# Bitcoin_Wallet.net
KiCad netlist of a schematic drawn in Altium Designer
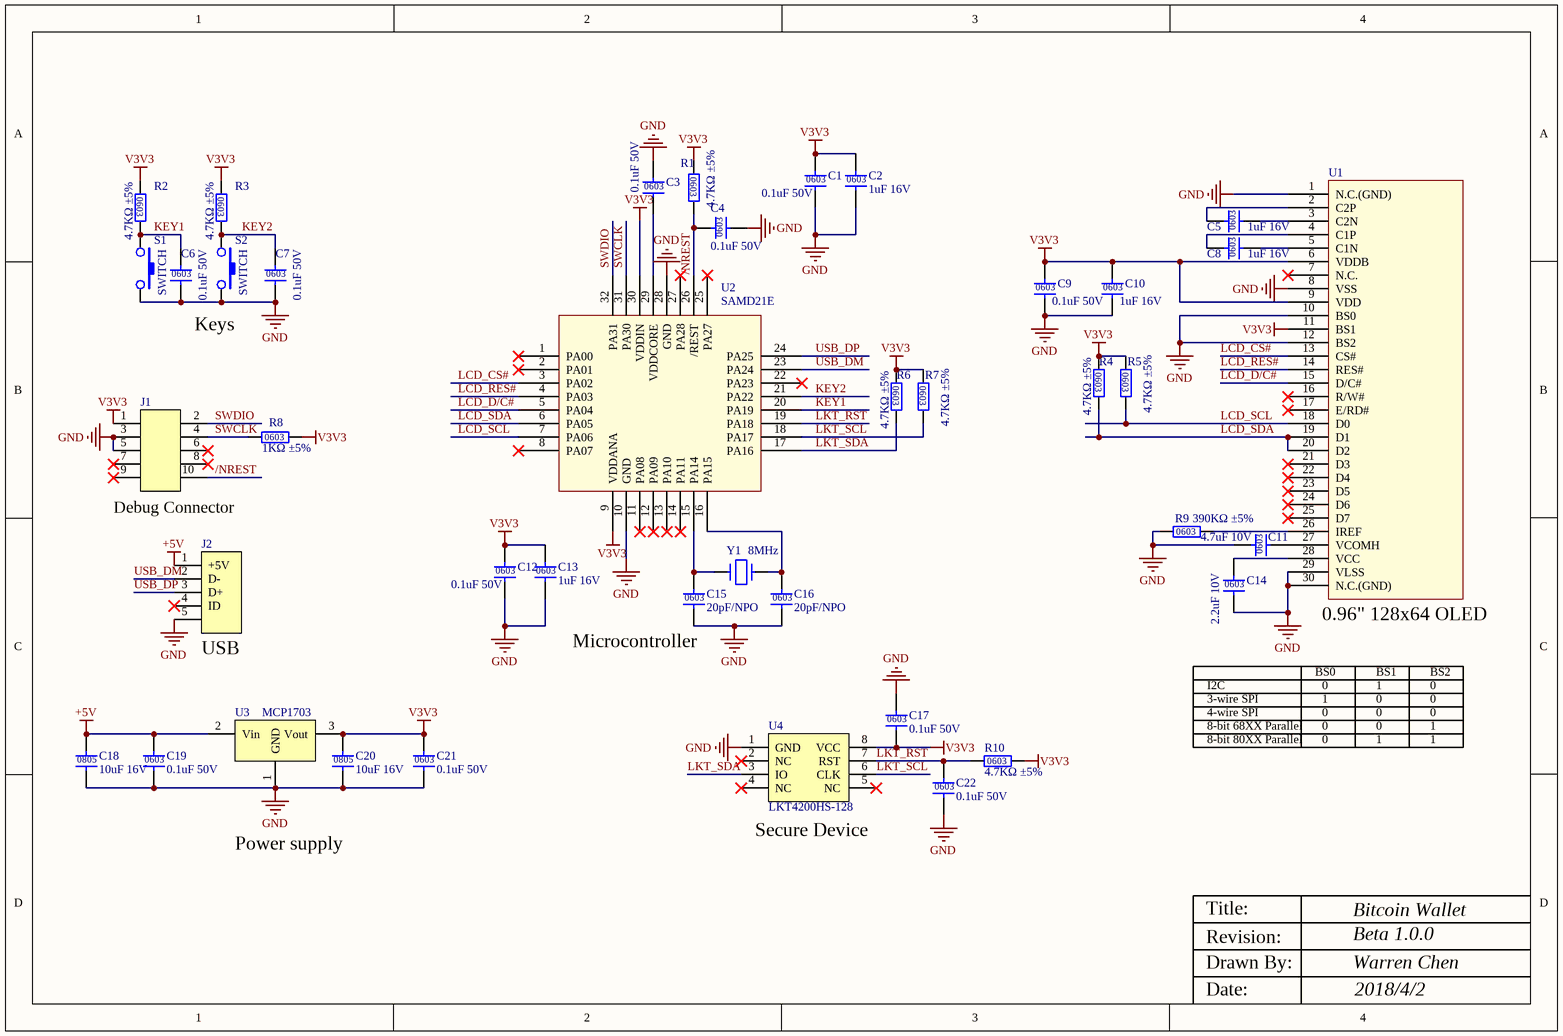
[diagram p0: Bitcoin Wallet.SchDoc]

(export (version "E")
  (design (tool "Eeschema 10.0.6"))
  (components
    (comp (ref "C1")
      (value "0.1uF 50V")
      (footprint "C-0603")
      (description "贴片电容 0.1uF 50V ±10% -55~+125℃ 0603 X7R CL10B104KB8NNNC")
      (libsource (lib "CLOU-BZ-BetaV0") (part "C-0.1uF 50V 0603"))
    )
    (comp (ref "C2")
      (value "1uF 16V")
      (footprint "C-0603")
      (description "贴片电容 1uF 16V ±10% -55~+125℃ 0603 X7R")
      (libsource (lib "CLOU-BZ-BetaV0") (part "C-1uF 16V 0603"))
    )
    (comp (ref "C3")
      (value "0.1uF 50V")
      (footprint "C-0603")
      (description "贴片电容 0.1uF 50V ±10% -55~+125℃ 0603 X7R CL10B104KB8NNNC")
      (libsource (lib "CLOU-BZ-BetaV0") (part "C-0.1uF 50V 0603"))
    )
    (comp (ref "C4")
      (value "0.1uF 50V")
      (footprint "C-0603")
      (description "贴片电容 0.1uF 50V ±10% -55~+125℃ 0603 X7R CL10B104KB8NNNC")
      (libsource (lib "CLOU-BZ-BetaV0") (part "C-0.1uF 50V 0603"))
    )
    (comp (ref "C5")
      (value "1uF 16V")
      (footprint "C-0603")
      (description "贴片电容 1uF 16V ±10% -55~+125℃ 0603 X7R")
      (libsource (lib "CLOU-BZ-BetaV0") (part "C-1uF 16V 0603"))
    )
    (comp (ref "C6")
      (value "0.1uF 50V")
      (footprint "C-0603")
      (description "贴片电容 0.1uF 50V ±10% -55~+125℃ 0603 X7R CL10B104KB8NNNC")
      (libsource (lib "CLOU-BZ-BetaV0") (part "C-0.1uF 50V 0603"))
    )
    (comp (ref "C7")
      (value "0.1uF 50V")
      (footprint "C-0603")
      (description "贴片电容 0.1uF 50V ±10% -55~+125℃ 0603 X7R CL10B104KB8NNNC")
      (libsource (lib "CLOU-BZ-BetaV0") (part "C-0.1uF 50V 0603"))
    )
    (comp (ref "C8")
      (value "1uF 16V")
      (footprint "C-0603")
      (description "贴片电容 1uF 16V ±10% -55~+125℃ 0603 X7R")
      (libsource (lib "CLOU-BZ-BetaV0") (part "C-1uF 16V 0603"))
    )
    (comp (ref "C9")
      (value "0.1uF 50V")
      (footprint "C-0603")
      (description "贴片电容 0.1uF 50V ±10% -55~+125℃ 0603 X7R CL10B104KB8NNNC")
      (libsource (lib "CLOU-BZ-BetaV0") (part "C-0.1uF 50V 0603"))
    )
    (comp (ref "C10")
      (value "1uF 16V")
      (footprint "C-0603")
      (description "贴片电容 1uF 16V ±10% -55~+125℃ 0603 X7R")
      (libsource (lib "CLOU-BZ-BetaV0") (part "C-1uF 16V 0603"))
    )
    (comp (ref "C11")
      (value "4.7uF 10V")
      (footprint "C-0603")
      (description "贴片电容 4.7uF 10V ±10% 0603 X5R")
      (libsource (lib "CLOU-BZ-BetaV0") (part "C-4.7uF 10V 0603"))
    )
    (comp (ref "C12")
      (value "0.1uF 50V")
      (footprint "C-0603")
      (description "贴片电容 0.1uF 50V ±10% -55~+125℃ 0603 X7R CL10B104KB8NNNC")
      (libsource (lib "CLOU-BZ-BetaV0") (part "C-0.1uF 50V 0603"))
    )
    (comp (ref "C13")
      (value "1uF 16V")
      (footprint "C-0603")
      (description "贴片电容 1uF 16V ±10% -55~+125℃ 0603 X7R")
      (libsource (lib "CLOU-BZ-BetaV0") (part "C-1uF 16V 0603"))
    )
    (comp (ref "C14")
      (value "2.2uF 10V")
      (footprint "C-0603")
      (description "贴片电容 2.2uF 10V ±10% 0603 X5R")
      (libsource (lib "CLOU-BZ-BetaV0") (part "C-2.2uF 10V 0603"))
    )
    (comp (ref "C15")
      (value "20pF/NPO")
      (footprint "C-0603")
      (description "贴片电容 20pF 50V ±5% -55~+125℃ 0603 NPO")
      (libsource (lib "CLOU-BZ-BetaV0") (part "C-20pF 50V 0603"))
    )
    (comp (ref "C16")
      (value "20pF/NPO")
      (footprint "C-0603")
      (description "贴片电容 20pF 50V ±5% -55~+125℃ 0603 NPO")
      (libsource (lib "CLOU-BZ-BetaV0") (part "C-20pF 50V 0603"))
    )
    (comp (ref "C17")
      (value "0.1uF 50V")
      (footprint "C-0603")
      (description "贴片电容 0.1uF 50V ±10% -55~+125℃ 0603 X7R CL10B104KB8NNNC")
      (libsource (lib "CLOU-BZ-BetaV0") (part "C-0.1uF 50V 0603"))
    )
    (comp (ref "C18")
      (value "10uF 16V")
      (footprint "C-0805")
      (description "贴片电容 10uF 16V ±10% -55~+125℃ 0805 X5R")
      (libsource (lib "CLOU-BZ-BetaV0") (part "C-10uF 16V 0805"))
    )
    (comp (ref "C19")
      (value "0.1uF 50V")
      (footprint "C-0603")
      (description "贴片电容 0.1uF 50V ±10% -55~+125℃ 0603 X7R CL10B104KB8NNNC")
      (libsource (lib "CLOU-BZ-BetaV0") (part "C-0.1uF 50V 0603"))
    )
    (comp (ref "C20")
      (value "10uF 16V")
      (footprint "C-0805")
      (description "贴片电容 10uF 16V ±10% -55~+125℃ 0805 X5R")
      (libsource (lib "CLOU-BZ-BetaV0") (part "C-10uF 16V 0805"))
    )
    (comp (ref "C21")
      (value "0.1uF 50V")
      (footprint "C-0603")
      (description "贴片电容 0.1uF 50V ±10% -55~+125℃ 0603 X7R CL10B104KB8NNNC")
      (libsource (lib "CLOU-BZ-BetaV0") (part "C-0.1uF 50V 0603"))
    )
    (comp (ref "C22")
      (value "0.1uF 50V")
      (footprint "C-0603")
      (description "贴片电容 0.1uF 50V ±10% -55~+125℃ 0603 X7R CL10B104KB8NNNC")
      (libsource (lib "CLOU-BZ-BetaV0") (part "C-0.1uF 50V 0603"))
    )
    (comp (ref "J1") (value "Debug Connector") (libsource (lib "SCHLIB") (part "CON2*5")))
    (comp (ref "J2") (value "USB") (libsource (lib "SCHLIB") (part "USB")))
    (comp (ref "R1")
      (value "4.7KΩ ±5%")
      (footprint "R-0603")
      (description "贴片电阻 4.7KΩ 1/10W ±5% ±200ppm 0603")
      (libsource (lib "CLOU-BZ-BetaV0") (part "R-4K7 0603 5%"))
    )
    (comp (ref "R2")
      (value "4.7KΩ ±5%")
      (footprint "R-0603")
      (description "贴片电阻 4.7KΩ 1/10W ±5% ±200ppm 0603")
      (libsource (lib "CLOU-BZ-BetaV0") (part "R-4K7 0603 5%"))
    )
    (comp (ref "R3")
      (value "4.7KΩ ±5%")
      (footprint "R-0603")
      (description "贴片电阻 4.7KΩ 1/10W ±5% ±200ppm 0603")
      (libsource (lib "CLOU-BZ-BetaV0") (part "R-4K7 0603 5%"))
    )
    (comp (ref "R4")
      (value "4.7KΩ ±5%")
      (footprint "R-0603")
      (description "贴片电阻 4.7KΩ 1/10W ±5% ±200ppm 0603")
      (libsource (lib "CLOU-BZ-BetaV0") (part "R-4K7 0603 5%"))
    )
    (comp (ref "R5")
      (value "4.7KΩ ±5%")
      (footprint "R-0603")
      (description "贴片电阻 4.7KΩ 1/10W ±5% ±200ppm 0603")
      (libsource (lib "CLOU-BZ-BetaV0") (part "R-4K7 0603 5%"))
    )
    (comp (ref "R6")
      (value "4.7KΩ ±5%")
      (footprint "R-0603")
      (description "贴片电阻 4.7KΩ 1/10W ±5% ±200ppm 0603")
      (libsource (lib "CLOU-BZ-BetaV0") (part "R-4K7 0603 5%"))
    )
    (comp (ref "R7")
      (value "4.7KΩ ±5%")
      (footprint "R-0603")
      (description "贴片电阻 4.7KΩ 1/10W ±5% ±200ppm 0603")
      (libsource (lib "CLOU-BZ-BetaV0") (part "R-4K7 0603 5%"))
    )
    (comp (ref "R8")
      (value "1KΩ ±5%")
      (footprint "R-0603")
      (description "贴片电阻 1KΩ 1/10W ±5% ±200ppm 0603")
      (libsource (lib "CLOU-BZ-BetaV0") (part "R-1K 0603 5%"))
    )
    (comp (ref "R9")
      (value "390KΩ ±5%")
      (footprint "R-0603")
      (description "贴片电阻 390KΩ 1/10W ±5% ±200ppm 0603")
      (libsource (lib "CLOU-BZ-BetaV0") (part "R-390K 0603 5%"))
    )
    (comp (ref "R10")
      (value "4.7KΩ ±5%")
      (footprint "R-0603")
      (description "贴片电阻 4.7KΩ 1/10W ±5% ±200ppm 0603")
      (libsource (lib "") (part "R-4K7 0603 5%_1"))
    )
    (comp (ref "S1")
      (value "SWITCH")
      (footprint "SW4-6X6-1")
      (description "开关（轻触）")
      (libsource (lib "NEW library") (part "SW_PB6.2*6.2_5"))
    )
    (comp (ref "S2")
      (value "SWITCH")
      (footprint "SW4-6X6-1")
      (description "开关（轻触）")
      (libsource (lib "NEW library") (part "SW_PB6.2*6.2_5"))
    )
    (comp (ref "U1") (value "0.96\" 128x64 OLED") (libsource (lib "SCHLIB") (part "Component_1")))
    (comp (ref "U2") (value "SAMD21E") (libsource (lib "SCHLIB") (part "SAMD21E")))
    (comp (ref "U3")
      (value "MCP1703")
      (footprint "IC-SOT-89")
      (description "HT7533-1 工业级 SOT-89 3.3V 100mA")
      (libsource (lib "CLOU-BZ-BetaV0") (part "U-HT7533-1"))
    )
    (comp (ref "U4") (value "LKT4200HS-128") (libsource (lib "SCHLIB") (part "LKT4200HS-128")))
    (comp (ref "Y1")
      (value "8MHz")
      (footprint "CRYSTAL2")
      (description "晶振")
      (libsource (lib "NEW library") (part "CRYSTAL_18.432M"))
    )
  )
  (nets
    (net (code "1") (name "+5V") (class "Default")
      (node (ref "C18") (pin "1") (pinfunction "1_1") (pintype "passive"))
      (node (ref "C19") (pin "1") (pinfunction "1_1") (pintype "passive"))
      (node (ref "J2") (pin "1") (pinfunction "+5V_1") (pintype "passive"))
      (node (ref "U3") (pin "2") (pinfunction "Vin_2") (pintype "passive"))
    )
    (net (code "2") (name "/KEY1") (class "Default")
      (node (ref "C6") (pin "1") (pinfunction "1_1") (pintype "passive"))
      (node (ref "R2") (pin "2") (pinfunction "2_2") (pintype "passive"))
      (node (ref "S1") (pin "2") (pinfunction "2_2") (pintype "passive"))
      (node (ref "U2") (pin "20") (pinfunction "PA19_20") (pintype "passive"))
    )
    (net (code "3") (name "/KEY2") (class "Default")
      (node (ref "C7") (pin "1") (pinfunction "1_1") (pintype "passive"))
      (node (ref "R3") (pin "2") (pinfunction "2_2") (pintype "passive"))
      (node (ref "S2") (pin "2") (pinfunction "2_2") (pintype "passive"))
      (node (ref "U2") (pin "21") (pinfunction "PA22_21") (pintype "passive"))
    )
    (net (code "4") (name "/LCD_CS#") (class "Default")
      (node (ref "U1") (pin "13") (pinfunction "CS#_13") (pintype "passive"))
      (node (ref "U2") (pin "3") (pinfunction "PA02_3") (pintype "passive"))
    )
    (net (code "5") (name "/LCD_D{slash}C#") (class "Default")
      (node (ref "U1") (pin "15") (pinfunction "D/C#_15") (pintype "passive"))
      (node (ref "U2") (pin "5") (pinfunction "PA04_5") (pintype "passive"))
    )
    (net (code "6") (name "/LCD_RES#") (class "Default")
      (node (ref "U1") (pin "14") (pinfunction "RES#_14") (pintype "passive"))
      (node (ref "U2") (pin "4") (pinfunction "PA03_4") (pintype "passive"))
    )
    (net (code "7") (name "/LCD_SCL") (class "Default")
      (node (ref "R5") (pin "2") (pinfunction "2_2") (pintype "passive"))
      (node (ref "U1") (pin "18") (pinfunction "D0_18") (pintype "passive"))
      (node (ref "U2") (pin "7") (pinfunction "PA06_7") (pintype "passive"))
    )
    (net (code "8") (name "/LCD_SDA") (class "Default")
      (node (ref "R4") (pin "2") (pinfunction "2_2") (pintype "passive"))
      (node (ref "U1") (pin "19") (pinfunction "D1_19") (pintype "passive"))
      (node (ref "U1") (pin "20") (pinfunction "D2_20") (pintype "passive"))
      (node (ref "U2") (pin "6") (pinfunction "PA05_6") (pintype "passive"))
    )
    (net (code "9") (name "/LKT_RST") (class "Default")
      (node (ref "C22") (pin "1") (pinfunction "1_1") (pintype "passive"))
      (node (ref "R10") (pin "1") (pinfunction "1_1") (pintype "passive"))
      (node (ref "U2") (pin "19") (pinfunction "PA18_19") (pintype "passive"))
      (node (ref "U4") (pin "7") (pinfunction "RST_7") (pintype "passive"))
    )
    (net (code "10") (name "/LKT_SCL") (class "Default")
      (node (ref "R7") (pin "2") (pinfunction "2_2") (pintype "passive"))
      (node (ref "U2") (pin "18") (pinfunction "PA17_18") (pintype "passive"))
      (node (ref "U4") (pin "6") (pinfunction "CLK_6") (pintype "passive"))
    )
    (net (code "11") (name "/LKT_SDA") (class "Default")
      (node (ref "R6") (pin "2") (pinfunction "2_2") (pintype "passive"))
      (node (ref "U2") (pin "17") (pinfunction "PA16_17") (pintype "passive"))
      (node (ref "U4") (pin "3") (pinfunction "IO_3") (pintype "passive"))
    )
    (net (code "12") (name "/SWCLK") (class "Default")
      (node (ref "J1") (pin "4") (pinfunction "4_4") (pintype "passive"))
      (node (ref "R8") (pin "1") (pinfunction "1_1") (pintype "passive"))
      (node (ref "U2") (pin "31") (pinfunction "PA30_31") (pintype "passive"))
    )
    (net (code "13") (name "/SWDIO") (class "Default")
      (node (ref "J1") (pin "2") (pinfunction "2_2") (pintype "passive"))
      (node (ref "U2") (pin "32") (pinfunction "PA31_32") (pintype "passive"))
    )
    (net (code "14") (name "/USB_DM") (class "Default")
      (node (ref "J2") (pin "2") (pinfunction "D-_2") (pintype "passive"))
      (node (ref "U2") (pin "23") (pinfunction "PA24_23") (pintype "passive"))
    )
    (net (code "15") (name "/USB_DP") (class "Default")
      (node (ref "J2") (pin "3") (pinfunction "D+_3") (pintype "passive"))
      (node (ref "U2") (pin "24") (pinfunction "PA25_24") (pintype "passive"))
    )
    (net (code "16") (name "/{slash}NREST") (class "Default")
      (node (ref "C4") (pin "1") (pinfunction "1_1") (pintype "passive"))
      (node (ref "R1") (pin "2") (pinfunction "2_2") (pintype "passive"))
      (node (ref "U2") (pin "26") (pinfunction "/REST_26") (pintype "passive"))
    )
    (net (code "17") (name "GND") (class "Default")
      (node (ref "C1") (pin "2") (pinfunction "2_2") (pintype "passive"))
      (node (ref "C10") (pin "2") (pinfunction "2_2") (pintype "passive"))
      (node (ref "C11") (pin "1") (pinfunction "1_1") (pintype "passive"))
      (node (ref "C12") (pin "2") (pinfunction "2_2") (pintype "passive"))
      (node (ref "C13") (pin "2") (pinfunction "2_2") (pintype "passive"))
      (node (ref "C14") (pin "2") (pinfunction "2_2") (pintype "passive"))
      (node (ref "C15") (pin "2") (pinfunction "2_2") (pintype "passive"))
      (node (ref "C16") (pin "2") (pinfunction "2_2") (pintype "passive"))
      (node (ref "C17") (pin "1") (pinfunction "1_1") (pintype "passive"))
      (node (ref "C18") (pin "2") (pinfunction "2_2") (pintype "passive"))
      (node (ref "C19") (pin "2") (pinfunction "2_2") (pintype "passive"))
      (node (ref "C2") (pin "2") (pinfunction "2_2") (pintype "passive"))
      (node (ref "C20") (pin "2") (pinfunction "2_2") (pintype "passive"))
      (node (ref "C21") (pin "2") (pinfunction "2_2") (pintype "passive"))
      (node (ref "C22") (pin "2") (pinfunction "2_2") (pintype "passive"))
      (node (ref "C3") (pin "1") (pinfunction "1_1") (pintype "passive"))
      (node (ref "C4") (pin "2") (pinfunction "2_2") (pintype "passive"))
      (node (ref "C6") (pin "2") (pinfunction "2_2") (pintype "passive"))
      (node (ref "C7") (pin "2") (pinfunction "2_2") (pintype "passive"))
      (node (ref "C9") (pin "2") (pinfunction "2_2") (pintype "passive"))
      (node (ref "J1") (pin "3") (pinfunction "3_3") (pintype "passive"))
      (node (ref "J1") (pin "5") (pinfunction "5_5") (pintype "passive"))
      (node (ref "J2") (pin "5") (pinfunction "GND_5") (pintype "passive"))
      (node (ref "R9") (pin "1") (pinfunction "1_1") (pintype "passive"))
      (node (ref "S1") (pin "1") (pinfunction "1_1") (pintype "passive"))
      (node (ref "S2") (pin "1") (pinfunction "1_1") (pintype "passive"))
      (node (ref "U1") (pin "1") (pinfunction "N.C.(GND)_1") (pintype "passive"))
      (node (ref "U1") (pin "10") (pinfunction "BS0_10") (pintype "passive"))
      (node (ref "U1") (pin "12") (pinfunction "BS2_12") (pintype "passive"))
      (node (ref "U1") (pin "29") (pinfunction "VLSS_29") (pintype "passive"))
      (node (ref "U1") (pin "30") (pinfunction "N.C.(GND)_30") (pintype "passive"))
      (node (ref "U1") (pin "8") (pinfunction "VSS_8") (pintype "passive"))
      (node (ref "U2") (pin "10") (pinfunction "GND_10") (pintype "passive"))
      (node (ref "U2") (pin "28") (pinfunction "GND_28") (pintype "passive"))
      (node (ref "U3") (pin "1") (pinfunction "GND_1") (pintype "passive"))
      (node (ref "U4") (pin "1") (pinfunction "GND_1") (pintype "passive"))
    )
    (net (code "18") (name "Net-(U1-C1N)") (class "Default")
      (node (ref "C8") (pin "2") (pinfunction "2_2") (pintype "passive"))
      (node (ref "U1") (pin "5") (pinfunction "C1N_5") (pintype "passive"))
    )
    (net (code "19") (name "Net-(U1-C1P)") (class "Default")
      (node (ref "C8") (pin "1") (pinfunction "1_1") (pintype "passive"))
      (node (ref "U1") (pin "4") (pinfunction "C1P_4") (pintype "passive"))
    )
    (net (code "20") (name "Net-(U1-C2N)") (class "Default")
      (node (ref "C5") (pin "2") (pinfunction "2_2") (pintype "passive"))
      (node (ref "U1") (pin "3") (pinfunction "C2N_3") (pintype "passive"))
    )
    (net (code "21") (name "Net-(U1-C2P)") (class "Default")
      (node (ref "C5") (pin "1") (pinfunction "1_1") (pintype "passive"))
      (node (ref "U1") (pin "2") (pinfunction "C2P_2") (pintype "passive"))
    )
    (net (code "22") (name "Net-(U1-IREF)") (class "Default")
      (node (ref "R9") (pin "2") (pinfunction "2_2") (pintype "passive"))
      (node (ref "U1") (pin "26") (pinfunction "IREF_26") (pintype "passive"))
    )
    (net (code "23") (name "Net-(U1-VCC)") (class "Default")
      (node (ref "C14") (pin "1") (pinfunction "1_1") (pintype "passive"))
      (node (ref "U1") (pin "28") (pinfunction "VCC_28") (pintype "passive"))
    )
    (net (code "24") (name "Net-(U1-VCOMH)") (class "Default")
      (node (ref "C11") (pin "2") (pinfunction "2_2") (pintype "passive"))
      (node (ref "U1") (pin "27") (pinfunction "VCOMH_27") (pintype "passive"))
    )
    (net (code "25") (name "Net-(U2-PA14)") (class "Default")
      (node (ref "C15") (pin "1") (pinfunction "1_1") (pintype "passive"))
      (node (ref "U2") (pin "15") (pinfunction "PA14_15") (pintype "passive"))
      (node (ref "Y1") (pin "3") (pinfunction "3_3") (pintype "passive"))
    )
    (net (code "26") (name "Net-(U2-PA15)") (class "Default")
      (node (ref "C16") (pin "1") (pinfunction "1_1") (pintype "passive"))
      (node (ref "U2") (pin "16") (pinfunction "PA15_16") (pintype "passive"))
      (node (ref "Y1") (pin "1") (pinfunction "1_1") (pintype "passive"))
    )
    (net (code "27") (name "Net-(U2-VDDCORE)") (class "Default")
      (node (ref "C3") (pin "2") (pinfunction "2_2") (pintype "passive"))
      (node (ref "U2") (pin "29") (pinfunction "VDDCORE_29") (pintype "passive"))
    )
    (net (code "28") (name "V3V3") (class "Default")
      (node (ref "C1") (pin "1") (pinfunction "1_1") (pintype "passive"))
      (node (ref "C10") (pin "1") (pinfunction "1_1") (pintype "passive"))
      (node (ref "C12") (pin "1") (pinfunction "1_1") (pintype "passive"))
      (node (ref "C13") (pin "1") (pinfunction "1_1") (pintype "passive"))
      (node (ref "C17") (pin "2") (pinfunction "2_2") (pintype "passive"))
      (node (ref "C2") (pin "1") (pinfunction "1_1") (pintype "passive"))
      (node (ref "C20") (pin "1") (pinfunction "1_1") (pintype "passive"))
      (node (ref "C21") (pin "1") (pinfunction "1_1") (pintype "passive"))
      (node (ref "C9") (pin "1") (pinfunction "1_1") (pintype "passive"))
      (node (ref "J1") (pin "1") (pinfunction "1_1") (pintype "passive"))
      (node (ref "R1") (pin "1") (pinfunction "1_1") (pintype "passive"))
      (node (ref "R10") (pin "2") (pinfunction "2_2") (pintype "passive"))
      (node (ref "R2") (pin "1") (pinfunction "1_1") (pintype "passive"))
      (node (ref "R3") (pin "1") (pinfunction "1_1") (pintype "passive"))
      (node (ref "R4") (pin "1") (pinfunction "1_1") (pintype "passive"))
      (node (ref "R5") (pin "1") (pinfunction "1_1") (pintype "passive"))
      (node (ref "R6") (pin "1") (pinfunction "1_1") (pintype "passive"))
      (node (ref "R7") (pin "1") (pinfunction "1_1") (pintype "passive"))
      (node (ref "R8") (pin "2") (pinfunction "2_2") (pintype "passive"))
      (node (ref "U1") (pin "11") (pinfunction "BS1_11") (pintype "passive"))
      (node (ref "U1") (pin "6") (pinfunction "VDDB_6") (pintype "passive"))
      (node (ref "U1") (pin "9") (pinfunction "VDD_9") (pintype "passive"))
      (node (ref "U2") (pin "30") (pinfunction "VDDIN_30") (pintype "passive"))
      (node (ref "U2") (pin "9") (pinfunction "VDDANA_9") (pintype "passive"))
      (node (ref "U3") (pin "3") (pinfunction "Vout_3") (pintype "passive"))
      (node (ref "U4") (pin "8") (pinfunction "VCC_8") (pintype "passive"))
    )
    (net (code "29") (name "unconnected-(J1-Pad6)") (class "Default")
      (node (ref "J1") (pin "6") (pinfunction "6_6") (pintype "passive+no_connect"))
    )
    (net (code "30") (name "unconnected-(J1-Pad7)") (class "Default")
      (node (ref "J1") (pin "7") (pinfunction "7_7") (pintype "passive+no_connect"))
    )
    (net (code "31") (name "unconnected-(J1-Pad8)") (class "Default")
      (node (ref "J1") (pin "8") (pinfunction "8_8") (pintype "passive+no_connect"))
    )
    (net (code "32") (name "unconnected-(J1-Pad9)") (class "Default")
      (node (ref "J1") (pin "9") (pinfunction "9_9") (pintype "passive+no_connect"))
    )
    (net (code "33") (name "unconnected-(J1-Pad10)") (class "Default")
      (node (ref "J1") (pin "10") (pinfunction "10_10") (pintype "passive"))
    )
    (net (code "34") (name "unconnected-(J2-ID-Pad4)") (class "Default")
      (node (ref "J2") (pin "4") (pinfunction "ID_4") (pintype "passive+no_connect"))
    )
    (net (code "35") (name "unconnected-(U1-D3-Pad21)") (class "Default")
      (node (ref "U1") (pin "21") (pinfunction "D3_21") (pintype "passive+no_connect"))
    )
    (net (code "36") (name "unconnected-(U1-D4-Pad22)") (class "Default")
      (node (ref "U1") (pin "22") (pinfunction "D4_22") (pintype "passive+no_connect"))
    )
    (net (code "37") (name "unconnected-(U1-D5-Pad23)") (class "Default")
      (node (ref "U1") (pin "23") (pinfunction "D5_23") (pintype "passive+no_connect"))
    )
    (net (code "38") (name "unconnected-(U1-D6-Pad24)") (class "Default")
      (node (ref "U1") (pin "24") (pinfunction "D6_24") (pintype "passive+no_connect"))
    )
    (net (code "39") (name "unconnected-(U1-D7-Pad25)") (class "Default")
      (node (ref "U1") (pin "25") (pinfunction "D7_25") (pintype "passive+no_connect"))
    )
    (net (code "40") (name "unconnected-(U1-E{slash}RD#-Pad17)") (class "Default")
      (node (ref "U1") (pin "17") (pinfunction "E/RD#_17") (pintype "passive+no_connect"))
    )
    (net (code "41") (name "unconnected-(U1-N.C.-Pad7)") (class "Default")
      (node (ref "U1") (pin "7") (pinfunction "N.C._7") (pintype "passive+no_connect"))
    )
    (net (code "42") (name "unconnected-(U1-R{slash}W#-Pad16)") (class "Default")
      (node (ref "U1") (pin "16") (pinfunction "R/W#_16") (pintype "passive+no_connect"))
    )
    (net (code "43") (name "unconnected-(U2-PA00-Pad1)") (class "Default")
      (node (ref "U2") (pin "1") (pinfunction "PA00_1") (pintype "passive+no_connect"))
    )
    (net (code "44") (name "unconnected-(U2-PA01-Pad2)") (class "Default")
      (node (ref "U2") (pin "2") (pinfunction "PA01_2") (pintype "passive+no_connect"))
    )
    (net (code "45") (name "unconnected-(U2-PA07-Pad8)") (class "Default")
      (node (ref "U2") (pin "8") (pinfunction "PA07_8") (pintype "passive+no_connect"))
    )
    (net (code "46") (name "unconnected-(U2-PA08-Pad11)") (class "Default")
      (node (ref "U2") (pin "11") (pinfunction "PA08_11") (pintype "passive+no_connect"))
    )
    (net (code "47") (name "unconnected-(U2-PA09-Pad12)") (class "Default")
      (node (ref "U2") (pin "12") (pinfunction "PA09_12") (pintype "passive+no_connect"))
    )
    (net (code "48") (name "unconnected-(U2-PA10-Pad13)") (class "Default")
      (node (ref "U2") (pin "13") (pinfunction "PA10_13") (pintype "passive+no_connect"))
    )
    (net (code "49") (name "unconnected-(U2-PA11-Pad14)") (class "Default")
      (node (ref "U2") (pin "14") (pinfunction "PA11_14") (pintype "passive+no_connect"))
    )
    (net (code "50") (name "unconnected-(U2-PA23-Pad22)") (class "Default")
      (node (ref "U2") (pin "22") (pinfunction "PA23_22") (pintype "passive+no_connect"))
    )
    (net (code "51") (name "unconnected-(U2-PA27-Pad25)") (class "Default")
      (node (ref "U2") (pin "25") (pinfunction "PA27_25") (pintype "passive+no_connect"))
    )
    (net (code "52") (name "unconnected-(U2-PA28-Pad27)") (class "Default")
      (node (ref "U2") (pin "27") (pinfunction "PA28_27") (pintype "passive+no_connect"))
    )
    (net (code "53") (name "unconnected-(U4-NC-Pad2)") (class "Default")
      (node (ref "U4") (pin "2") (pinfunction "NC_2") (pintype "passive+no_connect"))
    )
    (net (code "54") (name "unconnected-(U4-NC-Pad4)") (class "Default")
      (node (ref "U4") (pin "4") (pinfunction "NC_4") (pintype "passive+no_connect"))
    )
    (net (code "55") (name "unconnected-(U4-NC-Pad5)") (class "Default")
      (node (ref "U4") (pin "5") (pinfunction "NC_5") (pintype "passive+no_connect"))
    )
  )
)
